# kingoftone.net
KiCad netlist of a schematic drawn in EAGLE
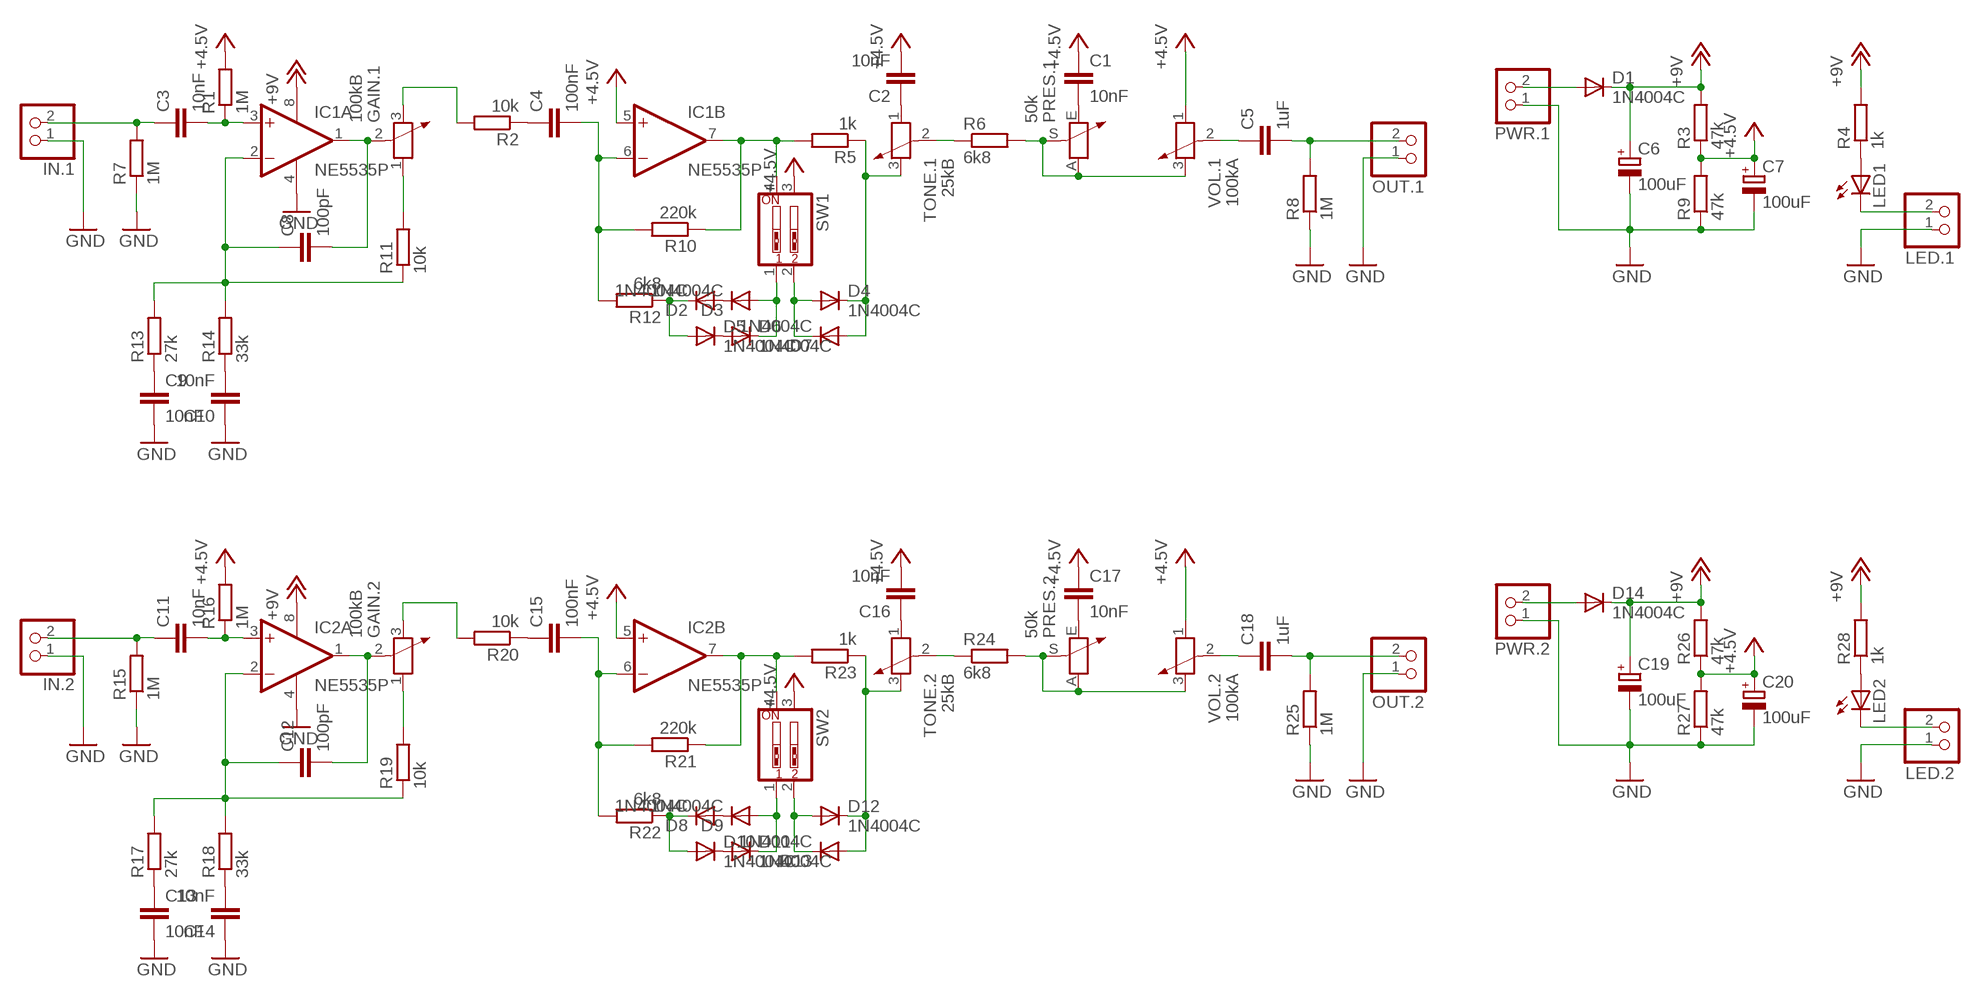
[diagram p0: schematic, sheet 1]

(export (version "E")
  (design (tool "Eeschema 10.0.6"))
  (components
    (comp (ref "C1")
      (value "10nF")
      (footprint "eagle-import:C050-025X075")
      (libsource (lib "eagle-import") (part "C-EU050-025X075"))
    )
    (comp (ref "C2")
      (value "10nF")
      (footprint "eagle-import:C050-025X075")
      (libsource (lib "eagle-import") (part "C-EU050-025X075"))
    )
    (comp (ref "C3")
      (value "10nF")
      (footprint "eagle-import:C050-025X075")
      (libsource (lib "eagle-import") (part "C-EU050-025X075"))
    )
    (comp (ref "C4")
      (value "100nF")
      (footprint "eagle-import:C050-025X075")
      (libsource (lib "eagle-import") (part "C-EU050-025X075"))
    )
    (comp (ref "C5")
      (value "1uF")
      (footprint "eagle-import:C050-025X075")
      (libsource (lib "eagle-import") (part "C-EU050-025X075"))
    )
    (comp (ref "C6")
      (value "100uF")
      (footprint "eagle-import:E2,5-6")
      (libsource (lib "eagle-import") (part "CPOL-EUE2.5-6"))
    )
    (comp (ref "C7")
      (value "100uF")
      (footprint "eagle-import:E2,5-6")
      (libsource (lib "eagle-import") (part "CPOL-EUE2.5-6"))
    )
    (comp (ref "C8")
      (value "100pF")
      (footprint "eagle-import:C050-025X075")
      (libsource (lib "eagle-import") (part "C-EU050-025X075"))
    )
    (comp (ref "C9")
      (value "10nF")
      (footprint "eagle-import:C050-025X075")
      (libsource (lib "eagle-import") (part "C-EU050-025X075"))
    )
    (comp (ref "C10")
      (value "10nF")
      (footprint "eagle-import:C050-025X075")
      (libsource (lib "eagle-import") (part "C-EU050-025X075"))
    )
    (comp (ref "C11")
      (value "10nF")
      (footprint "eagle-import:C050-025X075")
      (libsource (lib "eagle-import") (part "C-EU050-025X075"))
    )
    (comp (ref "C12")
      (value "100pF")
      (footprint "eagle-import:C050-025X075")
      (libsource (lib "eagle-import") (part "C-EU050-025X075"))
    )
    (comp (ref "C13")
      (value "10nF")
      (footprint "eagle-import:C050-025X075")
      (libsource (lib "eagle-import") (part "C-EU050-025X075"))
    )
    (comp (ref "C14")
      (value "10nF")
      (footprint "eagle-import:C050-025X075")
      (libsource (lib "eagle-import") (part "C-EU050-025X075"))
    )
    (comp (ref "C15")
      (value "100nF")
      (footprint "eagle-import:C050-025X075")
      (libsource (lib "eagle-import") (part "C-EU050-025X075"))
    )
    (comp (ref "C16")
      (value "10nF")
      (footprint "eagle-import:C050-025X075")
      (libsource (lib "eagle-import") (part "C-EU050-025X075"))
    )
    (comp (ref "C17")
      (value "10nF")
      (footprint "eagle-import:C050-025X075")
      (libsource (lib "eagle-import") (part "C-EU050-025X075"))
    )
    (comp (ref "C18")
      (value "1uF")
      (footprint "eagle-import:C050-025X075")
      (libsource (lib "eagle-import") (part "C-EU050-025X075"))
    )
    (comp (ref "C19")
      (value "100uF")
      (footprint "eagle-import:E2,5-6")
      (libsource (lib "eagle-import") (part "CPOL-EUE2.5-6"))
    )
    (comp (ref "C20")
      (value "100uF")
      (footprint "eagle-import:E2,5-6")
      (libsource (lib "eagle-import") (part "CPOL-EUE2.5-6"))
    )
    (comp (ref "D1")
      (value "1N4004C")
      (footprint "eagle-import:DO41-5")
      (libsource (lib "eagle-import") (part "1N4004C"))
    )
    (comp (ref "D2")
      (value "1N4004C")
      (footprint "eagle-import:DO41-5")
      (libsource (lib "eagle-import") (part "1N4004C"))
    )
    (comp (ref "D3")
      (value "1N4004C")
      (footprint "eagle-import:DO41-5")
      (libsource (lib "eagle-import") (part "1N4004C"))
    )
    (comp (ref "D4")
      (value "1N4004C")
      (footprint "eagle-import:DO41-5")
      (libsource (lib "eagle-import") (part "1N4004C"))
    )
    (comp (ref "D5")
      (value "1N4004C")
      (footprint "eagle-import:DO41-5")
      (libsource (lib "eagle-import") (part "1N4004C"))
    )
    (comp (ref "D6")
      (value "1N4004C")
      (footprint "eagle-import:DO41-5")
      (libsource (lib "eagle-import") (part "1N4004C"))
    )
    (comp (ref "D7")
      (value "1N4004C")
      (footprint "eagle-import:DO41-5")
      (libsource (lib "eagle-import") (part "1N4004C"))
    )
    (comp (ref "D8")
      (value "1N4004C")
      (footprint "eagle-import:DO41-5")
      (libsource (lib "eagle-import") (part "1N4004C"))
    )
    (comp (ref "D9")
      (value "1N4004C")
      (footprint "eagle-import:DO41-5")
      (libsource (lib "eagle-import") (part "1N4004C"))
    )
    (comp (ref "D10")
      (value "1N4004C")
      (footprint "eagle-import:DO41-5")
      (libsource (lib "eagle-import") (part "1N4004C"))
    )
    (comp (ref "D11")
      (value "1N4004C")
      (footprint "eagle-import:DO41-5")
      (libsource (lib "eagle-import") (part "1N4004C"))
    )
    (comp (ref "D12")
      (value "1N4004C")
      (footprint "eagle-import:DO41-5")
      (libsource (lib "eagle-import") (part "1N4004C"))
    )
    (comp (ref "D13")
      (value "1N4004C")
      (footprint "eagle-import:DO41-5")
      (libsource (lib "eagle-import") (part "1N4004C"))
    )
    (comp (ref "D14")
      (value "1N4004C")
      (footprint "eagle-import:DO41-5")
      (libsource (lib "eagle-import") (part "1N4004C"))
    )
    (comp (ref "GAIN.1")
      (value "100kB")
      (footprint "eagle-import:1X03")
      (libsource (lib "eagle-import") (part "POTENTIOMETER_"))
    )
    (comp (ref "GAIN.2")
      (value "100kB")
      (footprint "eagle-import:1X03")
      (libsource (lib "eagle-import") (part "POTENTIOMETER_"))
    )
    (comp (ref "IC1")
      (value "NE5535P")
      (footprint "eagle-import:DIL08")
      (libsource (lib "eagle-import") (part "NE5535P"))
    )
    (comp (ref "IC2")
      (value "NE5535P")
      (footprint "eagle-import:DIL08")
      (libsource (lib "eagle-import") (part "NE5535P"))
    )
    (comp (ref "IN.1")
      (value "PINHD-1X2")
      (footprint "eagle-import:1X02")
      (libsource (lib "eagle-import") (part "PINHD-1X2"))
    )
    (comp (ref "IN.2")
      (value "PINHD-1X2")
      (footprint "eagle-import:1X02")
      (libsource (lib "eagle-import") (part "PINHD-1X2"))
    )
    (comp (ref "LED.1")
      (value "PINHD-1X2")
      (footprint "eagle-import:1X02")
      (libsource (lib "eagle-import") (part "PINHD-1X2"))
    )
    (comp (ref "LED.2")
      (value "PINHD-1X2")
      (footprint "eagle-import:1X02")
      (libsource (lib "eagle-import") (part "PINHD-1X2"))
    )
    (comp (ref "LED1")
      (value "LED3MM")
      (footprint "eagle-import:LED3MM")
      (libsource (lib "eagle-import") (part "LED3MM"))
    )
    (comp (ref "LED2")
      (value "LED3MM")
      (footprint "eagle-import:LED3MM")
      (libsource (lib "eagle-import") (part "LED3MM"))
    )
    (comp (ref "OUT.1")
      (value "PINHD-1X2")
      (footprint "eagle-import:1X02")
      (libsource (lib "eagle-import") (part "PINHD-1X2"))
    )
    (comp (ref "OUT.2")
      (value "PINHD-1X2")
      (footprint "eagle-import:1X02")
      (libsource (lib "eagle-import") (part "PINHD-1X2"))
    )
    (comp (ref "PRES.1")
      (value "50k")
      (footprint "eagle-import:CT6")
      (libsource (lib "eagle-import") (part "POTENTIOMETER_CT6"))
    )
    (comp (ref "PRES.2")
      (value "50k")
      (footprint "eagle-import:CT6")
      (libsource (lib "eagle-import") (part "POTENTIOMETER_CT6"))
    )
    (comp (ref "PWR.1")
      (value "PINHD-1X2")
      (footprint "eagle-import:1X02")
      (libsource (lib "eagle-import") (part "PINHD-1X2"))
    )
    (comp (ref "PWR.2")
      (value "PINHD-1X2")
      (footprint "eagle-import:1X02")
      (libsource (lib "eagle-import") (part "PINHD-1X2"))
    )
    (comp (ref "R1")
      (value "1M")
      (footprint "eagle-import:0207_5V")
      (libsource (lib "eagle-import") (part "R-EU_0207/5V"))
    )
    (comp (ref "R2")
      (value "10k")
      (footprint "eagle-import:0207_5V")
      (libsource (lib "eagle-import") (part "R-EU_0207/5V"))
    )
    (comp (ref "R3")
      (value "47k")
      (footprint "eagle-import:0207_5V")
      (libsource (lib "eagle-import") (part "R-EU_0207/5V"))
    )
    (comp (ref "R4")
      (value "1k")
      (footprint "eagle-import:0207_5V")
      (libsource (lib "eagle-import") (part "R-EU_0207/5V"))
    )
    (comp (ref "R5")
      (value "1k")
      (footprint "eagle-import:0207_5V")
      (libsource (lib "eagle-import") (part "R-EU_0207/5V"))
    )
    (comp (ref "R6")
      (value "6k8")
      (footprint "eagle-import:0207_5V")
      (libsource (lib "eagle-import") (part "R-EU_0207/5V"))
    )
    (comp (ref "R7")
      (value "1M")
      (footprint "eagle-import:0207_5V")
      (libsource (lib "eagle-import") (part "R-EU_0207/5V"))
    )
    (comp (ref "R8")
      (value "1M")
      (footprint "eagle-import:0207_5V")
      (libsource (lib "eagle-import") (part "R-EU_0207/5V"))
    )
    (comp (ref "R9")
      (value "47k")
      (footprint "eagle-import:0207_5V")
      (libsource (lib "eagle-import") (part "R-EU_0207/5V"))
    )
    (comp (ref "R10")
      (value "220k")
      (footprint "eagle-import:0207_5V")
      (libsource (lib "eagle-import") (part "R-EU_0207/5V"))
    )
    (comp (ref "R11")
      (value "10k")
      (footprint "eagle-import:0207_5V")
      (libsource (lib "eagle-import") (part "R-EU_0207/5V"))
    )
    (comp (ref "R12")
      (value "6k8")
      (footprint "eagle-import:0207_5V")
      (libsource (lib "eagle-import") (part "R-EU_0207/5V"))
    )
    (comp (ref "R13")
      (value "27k")
      (footprint "eagle-import:0207_5V")
      (libsource (lib "eagle-import") (part "R-EU_0207/5V"))
    )
    (comp (ref "R14")
      (value "33k")
      (footprint "eagle-import:0207_5V")
      (libsource (lib "eagle-import") (part "R-EU_0207/5V"))
    )
    (comp (ref "R15")
      (value "1M")
      (footprint "eagle-import:0207_5V")
      (libsource (lib "eagle-import") (part "R-EU_0207/5V"))
    )
    (comp (ref "R16")
      (value "1M")
      (footprint "eagle-import:0207_5V")
      (libsource (lib "eagle-import") (part "R-EU_0207/5V"))
    )
    (comp (ref "R17")
      (value "27k")
      (footprint "eagle-import:0207_5V")
      (libsource (lib "eagle-import") (part "R-EU_0207/5V"))
    )
    (comp (ref "R18")
      (value "33k")
      (footprint "eagle-import:0207_5V")
      (libsource (lib "eagle-import") (part "R-EU_0207/5V"))
    )
    (comp (ref "R19")
      (value "10k")
      (footprint "eagle-import:0207_5V")
      (libsource (lib "eagle-import") (part "R-EU_0207/5V"))
    )
    (comp (ref "R20")
      (value "10k")
      (footprint "eagle-import:0207_5V")
      (libsource (lib "eagle-import") (part "R-EU_0207/5V"))
    )
    (comp (ref "R21")
      (value "220k")
      (footprint "eagle-import:0207_5V")
      (libsource (lib "eagle-import") (part "R-EU_0207/5V"))
    )
    (comp (ref "R22")
      (value "6k8")
      (footprint "eagle-import:0207_5V")
      (libsource (lib "eagle-import") (part "R-EU_0207/5V"))
    )
    (comp (ref "R23")
      (value "1k")
      (footprint "eagle-import:0207_5V")
      (libsource (lib "eagle-import") (part "R-EU_0207/5V"))
    )
    (comp (ref "R24")
      (value "6k8")
      (footprint "eagle-import:0207_5V")
      (libsource (lib "eagle-import") (part "R-EU_0207/5V"))
    )
    (comp (ref "R25")
      (value "1M")
      (footprint "eagle-import:0207_5V")
      (libsource (lib "eagle-import") (part "R-EU_0207/5V"))
    )
    (comp (ref "R26")
      (value "47k")
      (footprint "eagle-import:0207_5V")
      (libsource (lib "eagle-import") (part "R-EU_0207/5V"))
    )
    (comp (ref "R27")
      (value "47k")
      (footprint "eagle-import:0207_5V")
      (libsource (lib "eagle-import") (part "R-EU_0207/5V"))
    )
    (comp (ref "R28")
      (value "1k")
      (footprint "eagle-import:0207_5V")
      (libsource (lib "eagle-import") (part "R-EU_0207/5V"))
    )
    (comp (ref "SW1")
      (value "SW_DIP-2")
      (footprint "eagle-import:EDG-02")
      (libsource (lib "eagle-import") (part "SW_DIP-2"))
    )
    (comp (ref "SW2")
      (value "SW_DIP-2")
      (footprint "eagle-import:EDG-02")
      (libsource (lib "eagle-import") (part "SW_DIP-2"))
    )
    (comp (ref "TONE.1")
      (value "25kB")
      (footprint "eagle-import:1X03")
      (libsource (lib "eagle-import") (part "POTENTIOMETER_"))
    )
    (comp (ref "TONE.2")
      (value "25kB")
      (footprint "eagle-import:1X03")
      (libsource (lib "eagle-import") (part "POTENTIOMETER_"))
    )
    (comp (ref "VOL.1")
      (value "100kA")
      (footprint "eagle-import:1X03")
      (libsource (lib "eagle-import") (part "POTENTIOMETER_"))
    )
    (comp (ref "VOL.2")
      (value "100kA")
      (footprint "eagle-import:1X03")
      (libsource (lib "eagle-import") (part "POTENTIOMETER_"))
    )
  )
  (nets
    (net (code "1") (name "+4.5V") (class "Default")
      (node (ref "C1") (pin "1") (pinfunction "1_1") (pintype "passive"))
      (node (ref "C16") (pin "2") (pinfunction "2_2") (pintype "passive"))
      (node (ref "C17") (pin "1") (pinfunction "1_1") (pintype "passive"))
      (node (ref "C2") (pin "2") (pinfunction "2_2") (pintype "passive"))
      (node (ref "C20") (pin "+") (pinfunction "+_+") (pintype "passive"))
      (node (ref "C7") (pin "+") (pinfunction "+_+") (pintype "passive"))
      (node (ref "IC1") (pin "5") (pinfunction "+IN_5") (pintype "input"))
      (node (ref "IC2") (pin "5") (pinfunction "+IN_5") (pintype "input"))
      (node (ref "R1") (pin "2") (pinfunction "2_2") (pintype "passive"))
      (node (ref "R16") (pin "2") (pinfunction "2_2") (pintype "passive"))
      (node (ref "R26") (pin "1") (pinfunction "1_1") (pintype "passive"))
      (node (ref "R27") (pin "2") (pinfunction "2_2") (pintype "passive"))
      (node (ref "R3") (pin "1") (pinfunction "1_1") (pintype "passive"))
      (node (ref "R9") (pin "2") (pinfunction "2_2") (pintype "passive"))
      (node (ref "SW1") (pin "3") (pinfunction "3_3") (pintype "passive"))
      (node (ref "SW2") (pin "3") (pinfunction "3_3") (pintype "passive"))
      (node (ref "VOL.1") (pin "1") (pinfunction "1_1") (pintype "passive"))
      (node (ref "VOL.2") (pin "1") (pinfunction "1_1") (pintype "passive"))
    )
    (net (code "2") (name "+9V") (class "Default")
      (node (ref "C19") (pin "+") (pinfunction "+_+") (pintype "passive"))
      (node (ref "C6") (pin "+") (pinfunction "+_+") (pintype "passive"))
      (node (ref "D1") (pin "C") (pinfunction "C_C") (pintype "passive"))
      (node (ref "D14") (pin "C") (pinfunction "C_C") (pintype "passive"))
      (node (ref "IC1") (pin "8") (pinfunction "V+_8") (pintype "power_in"))
      (node (ref "IC2") (pin "8") (pinfunction "V+_8") (pintype "power_in"))
      (node (ref "R26") (pin "2") (pinfunction "2_2") (pintype "passive"))
      (node (ref "R28") (pin "2") (pinfunction "2_2") (pintype "passive"))
      (node (ref "R3") (pin "2") (pinfunction "2_2") (pintype "passive"))
      (node (ref "R4") (pin "2") (pinfunction "2_2") (pintype "passive"))
    )
    (net (code "3") (name "GND") (class "Default")
      (node (ref "C10") (pin "1") (pinfunction "1_1") (pintype "passive"))
      (node (ref "C13") (pin "2") (pinfunction "2_2") (pintype "passive"))
      (node (ref "C14") (pin "1") (pinfunction "1_1") (pintype "passive"))
      (node (ref "C19") (pin "-") (pinfunction "-_-") (pintype "passive"))
      (node (ref "C20") (pin "-") (pinfunction "-_-") (pintype "passive"))
      (node (ref "C6") (pin "-") (pinfunction "-_-") (pintype "passive"))
      (node (ref "C7") (pin "-") (pinfunction "-_-") (pintype "passive"))
      (node (ref "C9") (pin "2") (pinfunction "2_2") (pintype "passive"))
      (node (ref "IC1") (pin "4") (pinfunction "V-_4") (pintype "power_in"))
      (node (ref "IC2") (pin "4") (pinfunction "V-_4") (pintype "power_in"))
      (node (ref "IN.1") (pin "1") (pinfunction "1_1") (pintype "passive"))
      (node (ref "IN.2") (pin "1") (pinfunction "1_1") (pintype "passive"))
      (node (ref "LED.1") (pin "1") (pinfunction "1_1") (pintype "passive"))
      (node (ref "LED.2") (pin "1") (pinfunction "1_1") (pintype "passive"))
      (node (ref "OUT.1") (pin "1") (pinfunction "1_1") (pintype "passive"))
      (node (ref "OUT.2") (pin "1") (pinfunction "1_1") (pintype "passive"))
      (node (ref "PWR.1") (pin "1") (pinfunction "1_1") (pintype "passive"))
      (node (ref "PWR.2") (pin "1") (pinfunction "1_1") (pintype "passive"))
      (node (ref "R15") (pin "1") (pinfunction "1_1") (pintype "passive"))
      (node (ref "R25") (pin "1") (pinfunction "1_1") (pintype "passive"))
      (node (ref "R27") (pin "1") (pinfunction "1_1") (pintype "passive"))
      (node (ref "R7") (pin "1") (pinfunction "1_1") (pintype "passive"))
      (node (ref "R8") (pin "1") (pinfunction "1_1") (pintype "passive"))
      (node (ref "R9") (pin "1") (pinfunction "1_1") (pintype "passive"))
    )
    (net (code "4") (name "Net-(C2-Pad1)") (class "Default")
      (node (ref "C2") (pin "1") (pinfunction "1_1") (pintype "passive"))
      (node (ref "TONE.1") (pin "1") (pinfunction "1_1") (pintype "passive"))
    )
    (net (code "5") (name "Net-(C3-Pad1)") (class "Default")
      (node (ref "C3") (pin "1") (pinfunction "1_1") (pintype "passive"))
      (node (ref "IN.1") (pin "2") (pinfunction "2_2") (pintype "passive"))
      (node (ref "R7") (pin "2") (pinfunction "2_2") (pintype "passive"))
    )
    (net (code "6") (name "Net-(C4-Pad1)") (class "Default")
      (node (ref "C4") (pin "1") (pinfunction "1_1") (pintype "passive"))
      (node (ref "R2") (pin "1") (pinfunction "1_1") (pintype "passive"))
    )
    (net (code "7") (name "Net-(C5-Pad2)") (class "Default")
      (node (ref "C5") (pin "2") (pinfunction "2_2") (pintype "passive"))
      (node (ref "OUT.1") (pin "2") (pinfunction "2_2") (pintype "passive"))
      (node (ref "R8") (pin "2") (pinfunction "2_2") (pintype "passive"))
    )
    (net (code "8") (name "Net-(C9-Pad1)") (class "Default")
      (node (ref "C9") (pin "1") (pinfunction "1_1") (pintype "passive"))
      (node (ref "R13") (pin "1") (pinfunction "1_1") (pintype "passive"))
    )
    (net (code "9") (name "Net-(C10-Pad2)") (class "Default")
      (node (ref "C10") (pin "2") (pinfunction "2_2") (pintype "passive"))
      (node (ref "R14") (pin "1") (pinfunction "1_1") (pintype "passive"))
    )
    (net (code "10") (name "Net-(C11-Pad1)") (class "Default")
      (node (ref "C11") (pin "1") (pinfunction "1_1") (pintype "passive"))
      (node (ref "IN.2") (pin "2") (pinfunction "2_2") (pintype "passive"))
      (node (ref "R15") (pin "2") (pinfunction "2_2") (pintype "passive"))
    )
    (net (code "11") (name "Net-(C13-Pad1)") (class "Default")
      (node (ref "C13") (pin "1") (pinfunction "1_1") (pintype "passive"))
      (node (ref "R17") (pin "1") (pinfunction "1_1") (pintype "passive"))
    )
    (net (code "12") (name "Net-(C14-Pad2)") (class "Default")
      (node (ref "C14") (pin "2") (pinfunction "2_2") (pintype "passive"))
      (node (ref "R18") (pin "1") (pinfunction "1_1") (pintype "passive"))
    )
    (net (code "13") (name "Net-(C15-Pad1)") (class "Default")
      (node (ref "C15") (pin "1") (pinfunction "1_1") (pintype "passive"))
      (node (ref "R20") (pin "1") (pinfunction "1_1") (pintype "passive"))
    )
    (net (code "14") (name "Net-(C16-Pad1)") (class "Default")
      (node (ref "C16") (pin "1") (pinfunction "1_1") (pintype "passive"))
      (node (ref "TONE.2") (pin "1") (pinfunction "1_1") (pintype "passive"))
    )
    (net (code "15") (name "Net-(C18-Pad2)") (class "Default")
      (node (ref "C18") (pin "2") (pinfunction "2_2") (pintype "passive"))
      (node (ref "OUT.2") (pin "2") (pinfunction "2_2") (pintype "passive"))
      (node (ref "R25") (pin "2") (pinfunction "2_2") (pintype "passive"))
    )
    (net (code "16") (name "Net-(D1-PadA)") (class "Default")
      (node (ref "D1") (pin "A") (pinfunction "A_A") (pintype "passive"))
      (node (ref "PWR.1") (pin "2") (pinfunction "2_2") (pintype "passive"))
    )
    (net (code "17") (name "Net-(D2-PadA)") (class "Default")
      (node (ref "D2") (pin "A") (pinfunction "A_A") (pintype "passive"))
      (node (ref "D3") (pin "C") (pinfunction "C_C") (pintype "passive"))
    )
    (net (code "18") (name "Net-(D2-PadC)") (class "Default")
      (node (ref "D2") (pin "C") (pinfunction "C_C") (pintype "passive"))
      (node (ref "D5") (pin "A") (pinfunction "A_A") (pintype "passive"))
      (node (ref "R12") (pin "1") (pinfunction "1_1") (pintype "passive"))
    )
    (net (code "19") (name "Net-(D3-PadA)") (class "Default")
      (node (ref "D3") (pin "A") (pinfunction "A_A") (pintype "passive"))
      (node (ref "D6") (pin "C") (pinfunction "C_C") (pintype "passive"))
      (node (ref "SW1") (pin "1") (pinfunction "1_1") (pintype "passive"))
    )
    (net (code "20") (name "Net-(D4-PadA)") (class "Default")
      (node (ref "D4") (pin "A") (pinfunction "A_A") (pintype "passive"))
      (node (ref "D7") (pin "C") (pinfunction "C_C") (pintype "passive"))
      (node (ref "SW1") (pin "2") (pinfunction "2_2") (pintype "passive"))
    )
    (net (code "21") (name "Net-(D5-PadC)") (class "Default")
      (node (ref "D5") (pin "C") (pinfunction "C_C") (pintype "passive"))
      (node (ref "D6") (pin "A") (pinfunction "A_A") (pintype "passive"))
    )
    (net (code "22") (name "Net-(D8-PadA)") (class "Default")
      (node (ref "D8") (pin "A") (pinfunction "A_A") (pintype "passive"))
      (node (ref "D9") (pin "C") (pinfunction "C_C") (pintype "passive"))
    )
    (net (code "23") (name "Net-(D10-PadA)") (class "Default")
      (node (ref "D10") (pin "A") (pinfunction "A_A") (pintype "passive"))
      (node (ref "D8") (pin "C") (pinfunction "C_C") (pintype "passive"))
      (node (ref "R22") (pin "1") (pinfunction "1_1") (pintype "passive"))
    )
    (net (code "24") (name "Net-(D10-PadC)") (class "Default")
      (node (ref "D10") (pin "C") (pinfunction "C_C") (pintype "passive"))
      (node (ref "D11") (pin "A") (pinfunction "A_A") (pintype "passive"))
    )
    (net (code "25") (name "Net-(D11-PadC)") (class "Default")
      (node (ref "D11") (pin "C") (pinfunction "C_C") (pintype "passive"))
      (node (ref "D9") (pin "A") (pinfunction "A_A") (pintype "passive"))
      (node (ref "SW2") (pin "1") (pinfunction "1_1") (pintype "passive"))
    )
    (net (code "26") (name "Net-(D12-PadA)") (class "Default")
      (node (ref "D12") (pin "A") (pinfunction "A_A") (pintype "passive"))
      (node (ref "D13") (pin "C") (pinfunction "C_C") (pintype "passive"))
      (node (ref "SW2") (pin "2") (pinfunction "2_2") (pintype "passive"))
    )
    (net (code "27") (name "Net-(D14-PadA)") (class "Default")
      (node (ref "D14") (pin "A") (pinfunction "A_A") (pintype "passive"))
      (node (ref "PWR.2") (pin "2") (pinfunction "2_2") (pintype "passive"))
    )
    (net (code "28") (name "Net-(GAIN.1-2)") (class "Default")
      (node (ref "GAIN.1") (pin "3") (pinfunction "2_3") (pintype "passive"))
      (node (ref "R2") (pin "2") (pinfunction "2_2") (pintype "passive"))
    )
    (net (code "29") (name "Net-(GAIN.1-3)") (class "Default")
      (node (ref "C8") (pin "2") (pinfunction "2_2") (pintype "passive"))
      (node (ref "GAIN.1") (pin "2") (pinfunction "3_2") (pintype "passive"))
      (node (ref "IC1") (pin "1") (pinfunction "OUT_1") (pintype "output"))
    )
    (net (code "30") (name "Net-(GAIN.1-Pad1)") (class "Default")
      (node (ref "GAIN.1") (pin "1") (pinfunction "1_1") (pintype "passive"))
      (node (ref "R11") (pin "2") (pinfunction "2_2") (pintype "passive"))
    )
    (net (code "31") (name "Net-(GAIN.2-2)") (class "Default")
      (node (ref "GAIN.2") (pin "3") (pinfunction "2_3") (pintype "passive"))
      (node (ref "R20") (pin "2") (pinfunction "2_2") (pintype "passive"))
    )
    (net (code "32") (name "Net-(GAIN.2-3)") (class "Default")
      (node (ref "C12") (pin "2") (pinfunction "2_2") (pintype "passive"))
      (node (ref "GAIN.2") (pin "2") (pinfunction "3_2") (pintype "passive"))
      (node (ref "IC2") (pin "1") (pinfunction "OUT_1") (pintype "output"))
    )
    (net (code "33") (name "Net-(GAIN.2-Pad1)") (class "Default")
      (node (ref "GAIN.2") (pin "1") (pinfunction "1_1") (pintype "passive"))
      (node (ref "R19") (pin "2") (pinfunction "2_2") (pintype "passive"))
    )
    (net (code "34") (name "Net-(IC1A-+IN)") (class "Default")
      (node (ref "C3") (pin "2") (pinfunction "2_2") (pintype "passive"))
      (node (ref "IC1") (pin "3") (pinfunction "+IN_3") (pintype "input"))
      (node (ref "R1") (pin "1") (pinfunction "1_1") (pintype "passive"))
    )
    (net (code "35") (name "Net-(IC1A--IN)") (class "Default")
      (node (ref "C8") (pin "1") (pinfunction "1_1") (pintype "passive"))
      (node (ref "IC1") (pin "2") (pinfunction "-IN_2") (pintype "input"))
      (node (ref "R11") (pin "1") (pinfunction "1_1") (pintype "passive"))
      (node (ref "R13") (pin "2") (pinfunction "2_2") (pintype "passive"))
      (node (ref "R14") (pin "2") (pinfunction "2_2") (pintype "passive"))
    )
    (net (code "36") (name "Net-(IC1B--IN)") (class "Default")
      (node (ref "C4") (pin "2") (pinfunction "2_2") (pintype "passive"))
      (node (ref "IC1") (pin "6") (pinfunction "-IN_6") (pintype "input"))
      (node (ref "R10") (pin "2") (pinfunction "2_2") (pintype "passive"))
      (node (ref "R12") (pin "2") (pinfunction "2_2") (pintype "passive"))
    )
    (net (code "37") (name "Net-(IC1B-OUT)") (class "Default")
      (node (ref "IC1") (pin "7") (pinfunction "OUT_7") (pintype "output"))
      (node (ref "R10") (pin "1") (pinfunction "1_1") (pintype "passive"))
      (node (ref "R5") (pin "2") (pinfunction "2_2") (pintype "passive"))
      (node (ref "SW1") (pin "4") (pinfunction "4_4") (pintype "passive"))
    )
    (net (code "38") (name "Net-(IC2A-+IN)") (class "Default")
      (node (ref "C11") (pin "2") (pinfunction "2_2") (pintype "passive"))
      (node (ref "IC2") (pin "3") (pinfunction "+IN_3") (pintype "input"))
      (node (ref "R16") (pin "1") (pinfunction "1_1") (pintype "passive"))
    )
    (net (code "39") (name "Net-(IC2A--IN)") (class "Default")
      (node (ref "C12") (pin "1") (pinfunction "1_1") (pintype "passive"))
      (node (ref "IC2") (pin "2") (pinfunction "-IN_2") (pintype "input"))
      (node (ref "R17") (pin "2") (pinfunction "2_2") (pintype "passive"))
      (node (ref "R18") (pin "2") (pinfunction "2_2") (pintype "passive"))
      (node (ref "R19") (pin "1") (pinfunction "1_1") (pintype "passive"))
    )
    (net (code "40") (name "Net-(IC2B--IN)") (class "Default")
      (node (ref "C15") (pin "2") (pinfunction "2_2") (pintype "passive"))
      (node (ref "IC2") (pin "6") (pinfunction "-IN_6") (pintype "input"))
      (node (ref "R21") (pin "2") (pinfunction "2_2") (pintype "passive"))
      (node (ref "R22") (pin "2") (pinfunction "2_2") (pintype "passive"))
    )
    (net (code "41") (name "Net-(IC2B-OUT)") (class "Default")
      (node (ref "IC2") (pin "7") (pinfunction "OUT_7") (pintype "output"))
      (node (ref "R21") (pin "1") (pinfunction "1_1") (pintype "passive"))
      (node (ref "R23") (pin "2") (pinfunction "2_2") (pintype "passive"))
      (node (ref "SW2") (pin "4") (pinfunction "4_4") (pintype "passive"))
    )
    (net (code "42") (name "Net-(LED1-C)") (class "Default")
      (node (ref "LED.1") (pin "2") (pinfunction "2_2") (pintype "passive"))
      (node (ref "LED1") (pin "K") (pinfunction "C_K") (pintype "passive"))
    )
    (net (code "43") (name "Net-(LED1-PadA)") (class "Default")
      (node (ref "LED1") (pin "A") (pinfunction "A_A") (pintype "passive"))
      (node (ref "R4") (pin "1") (pinfunction "1_1") (pintype "passive"))
    )
    (net (code "44") (name "Net-(LED2-C)") (class "Default")
      (node (ref "LED.2") (pin "2") (pinfunction "2_2") (pintype "passive"))
      (node (ref "LED2") (pin "K") (pinfunction "C_K") (pintype "passive"))
    )
    (net (code "45") (name "Net-(LED2-PadA)") (class "Default")
      (node (ref "LED2") (pin "A") (pinfunction "A_A") (pintype "passive"))
      (node (ref "R28") (pin "1") (pinfunction "1_1") (pintype "passive"))
    )
    (net (code "46") (name "Net-(PRES.1-1)") (class "Default")
      (node (ref "PRES.1") (pin "A") (pinfunction "1_A") (pintype "passive"))
      (node (ref "PRES.1") (pin "S") (pinfunction "3_S") (pintype "passive"))
      (node (ref "R6") (pin "2") (pinfunction "2_2") (pintype "passive"))
      (node (ref "VOL.1") (pin "3") (pinfunction "2_3") (pintype "passive"))
    )
    (net (code "47") (name "Net-(PRES.1-2)") (class "Default")
      (node (ref "C1") (pin "2") (pinfunction "2_2") (pintype "passive"))
      (node (ref "PRES.1") (pin "E") (pinfunction "2_E") (pintype "passive"))
    )
    (net (code "48") (name "Net-(PRES.2-1)") (class "Default")
      (node (ref "PRES.2") (pin "A") (pinfunction "1_A") (pintype "passive"))
      (node (ref "PRES.2") (pin "S") (pinfunction "3_S") (pintype "passive"))
      (node (ref "R24") (pin "2") (pinfunction "2_2") (pintype "passive"))
      (node (ref "VOL.2") (pin "3") (pinfunction "2_3") (pintype "passive"))
    )
    (net (code "49") (name "Net-(PRES.2-2)") (class "Default")
      (node (ref "C17") (pin "2") (pinfunction "2_2") (pintype "passive"))
      (node (ref "PRES.2") (pin "E") (pinfunction "2_E") (pintype "passive"))
    )
    (net (code "50") (name "Net-(TONE.1-2)") (class "Default")
      (node (ref "D4") (pin "C") (pinfunction "C_C") (pintype "passive"))
      (node (ref "D7") (pin "A") (pinfunction "A_A") (pintype "passive"))
      (node (ref "R5") (pin "1") (pinfunction "1_1") (pintype "passive"))
      (node (ref "TONE.1") (pin "3") (pinfunction "2_3") (pintype "passive"))
    )
    (net (code "51") (name "Net-(TONE.1-3)") (class "Default")
      (node (ref "R6") (pin "1") (pinfunction "1_1") (pintype "passive"))
      (node (ref "TONE.1") (pin "2") (pinfunction "3_2") (pintype "passive"))
    )
    (net (code "52") (name "Net-(TONE.2-2)") (class "Default")
      (node (ref "D12") (pin "C") (pinfunction "C_C") (pintype "passive"))
      (node (ref "D13") (pin "A") (pinfunction "A_A") (pintype "passive"))
      (node (ref "R23") (pin "1") (pinfunction "1_1") (pintype "passive"))
      (node (ref "TONE.2") (pin "3") (pinfunction "2_3") (pintype "passive"))
    )
    (net (code "53") (name "Net-(TONE.2-3)") (class "Default")
      (node (ref "R24") (pin "1") (pinfunction "1_1") (pintype "passive"))
      (node (ref "TONE.2") (pin "2") (pinfunction "3_2") (pintype "passive"))
    )
    (net (code "54") (name "Net-(VOL.1-3)") (class "Default")
      (node (ref "C5") (pin "1") (pinfunction "1_1") (pintype "passive"))
      (node (ref "VOL.1") (pin "2") (pinfunction "3_2") (pintype "passive"))
    )
    (net (code "55") (name "Net-(VOL.2-3)") (class "Default")
      (node (ref "C18") (pin "1") (pinfunction "1_1") (pintype "passive"))
      (node (ref "VOL.2") (pin "2") (pinfunction "3_2") (pintype "passive"))
    )
  )
)
